# LED_for_Junction_Box.net
KiCad netlist of a schematic drawn in EAGLE
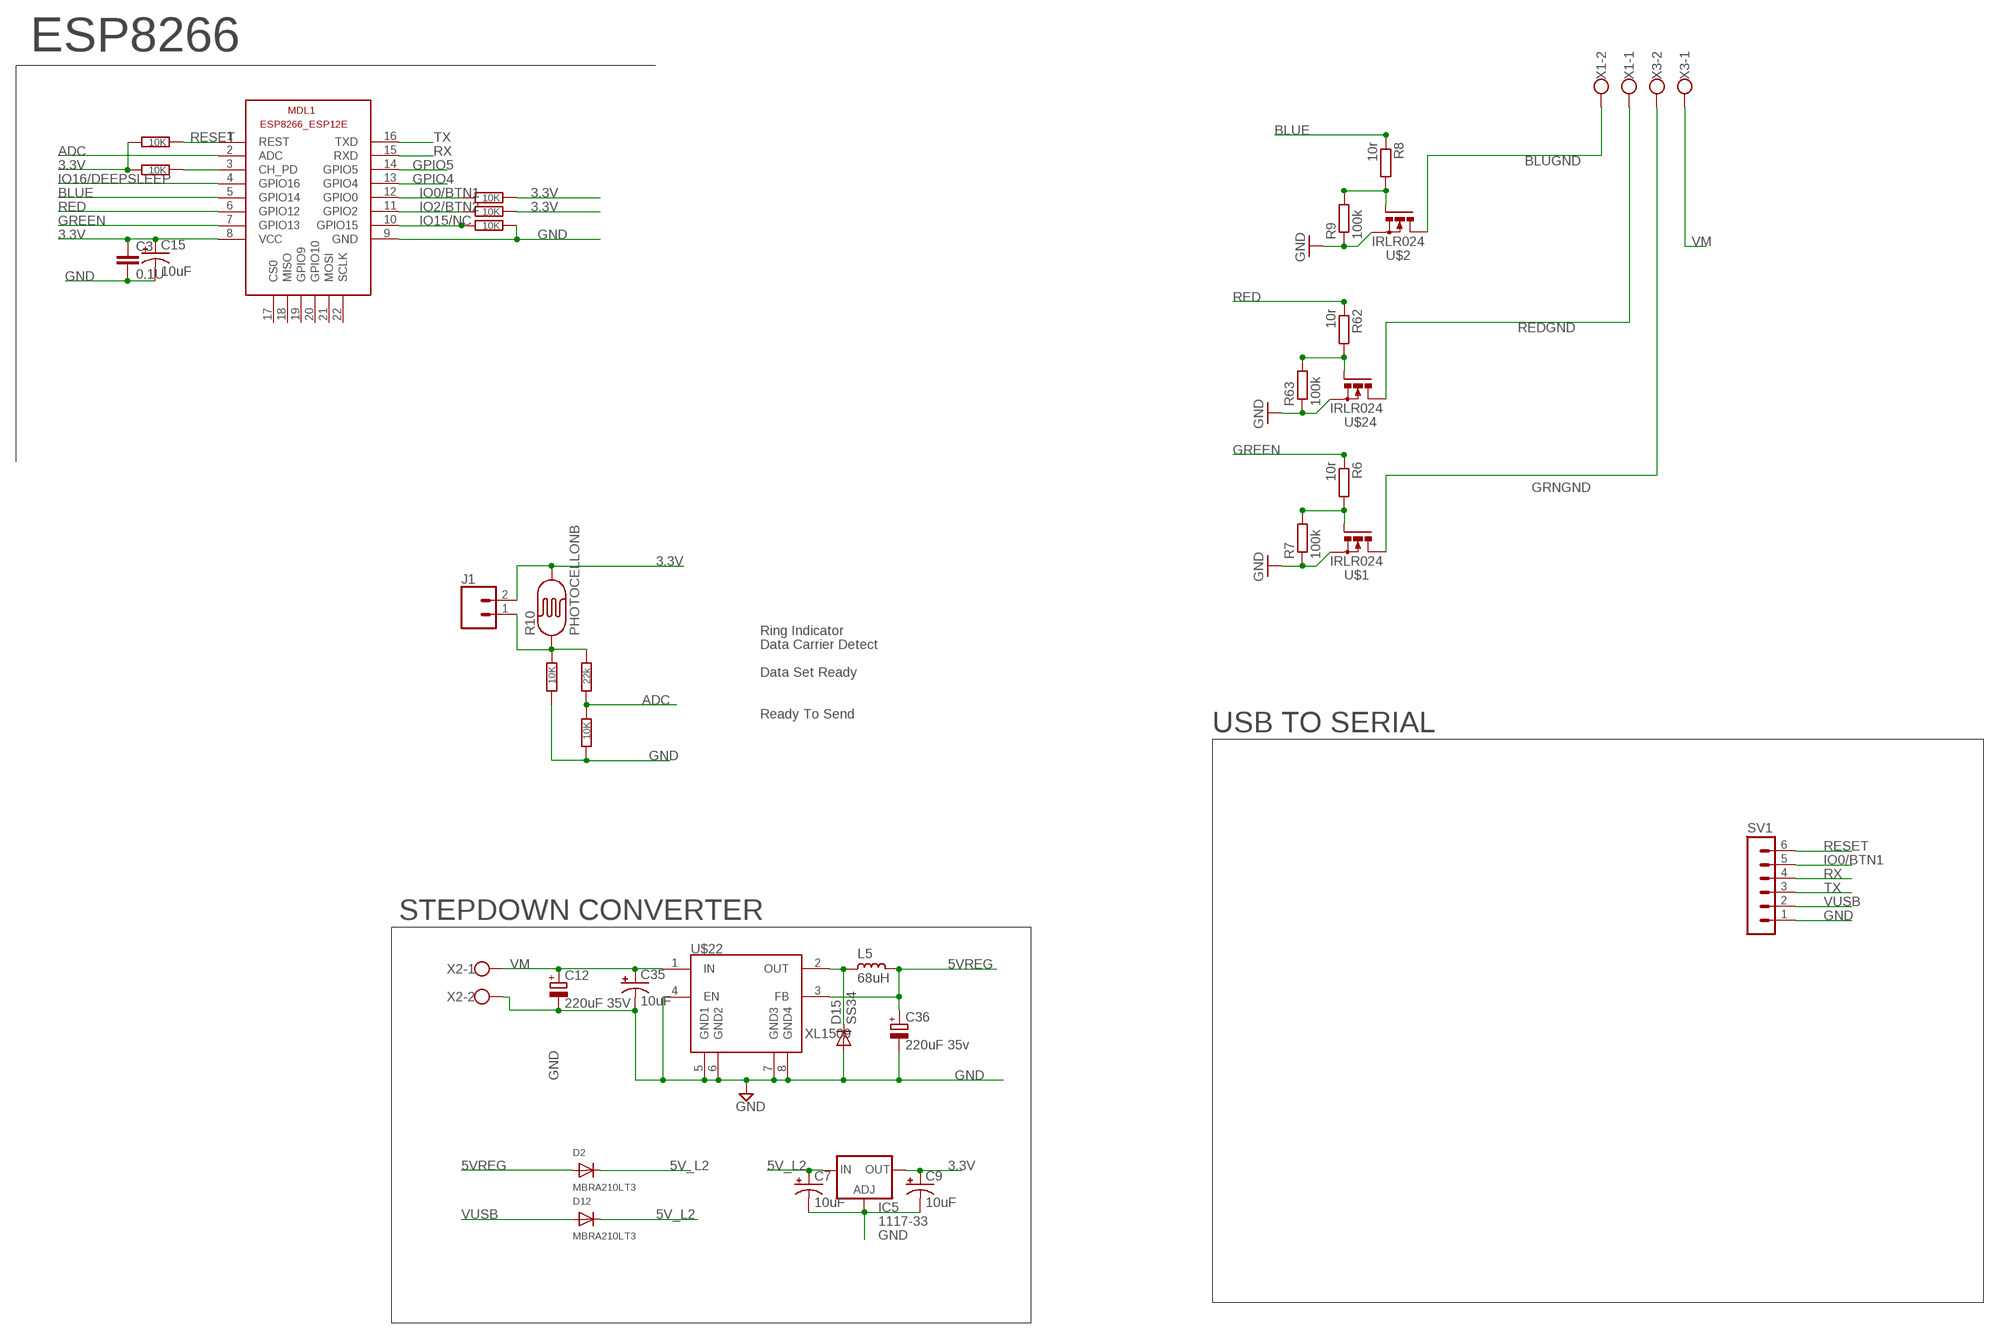
[diagram p0: schematic, sheet 1]

(export (version "E")
  (design (tool "Eeschema 10.0.6"))
  (components
    (comp (ref "C3")
      (value "0.1U")
      (footprint "eagle-import:C1206")
      (libsource (lib "eagle-import") (part "C-EUC1206"))
    )
    (comp (ref "C7")
      (value "10uF")
      (footprint "eagle-import:EIA3216")
      (libsource (lib "eagle-import") (part "CAP_POL1206"))
    )
    (comp (ref "C9")
      (value "10uF")
      (footprint "eagle-import:EIA3216")
      (libsource (lib "eagle-import") (part "CAP_POL1206"))
    )
    (comp (ref "C12")
      (value "220uF 35V")
      (footprint "eagle-import:E3,5-8")
      (libsource (lib "eagle-import") (part "CPOL-EUE3.5-8"))
    )
    (comp (ref "C15")
      (value "10uF")
      (footprint "eagle-import:EIA3216")
      (libsource (lib "eagle-import") (part "CAP_POL1206"))
    )
    (comp (ref "C35")
      (value "10uF")
      (footprint "eagle-import:EIA3216")
      (libsource (lib "eagle-import") (part "CAP_POL1206"))
    )
    (comp (ref "C36")
      (value "220uF 35v")
      (footprint "eagle-import:E3,5-8")
      (libsource (lib "eagle-import") (part "CPOL-EUE3.5-8"))
    )
    (comp (ref "D2")
      (value "MBRA210LT3")
      (footprint "eagle-import:SMADIODE")
      (libsource (lib "eagle-import") (part "DIODESMA"))
    )
    (comp (ref "D12")
      (value "MBRA210LT3")
      (footprint "eagle-import:SMADIODE")
      (libsource (lib "eagle-import") (part "DIODESMA"))
    )
    (comp (ref "D15")
      (value "SS34")
      (footprint "eagle-import:DO-214AC")
      (libsource (lib "eagle-import") (part "DIODE-DO-214AC"))
    )
    (comp (ref "IC5")
      (value "1117-33")
      (footprint "eagle-import:SOT223")
      (libsource (lib "eagle-import") (part "LD117A?S33TR"))
    )
    (comp (ref "J1")
      (value "CONN_02LOCK")
      (footprint "eagle-import:1X02_LOCK")
      (libsource (lib "eagle-import") (part "CONN_02LOCK"))
    )
    (comp (ref "L5")
      (value "68uH")
      (footprint "eagle-import:CD75")
      (libsource (lib "eagle-import") (part "L_CD75"))
    )
    (comp (ref "MDL1")
      (value "ESP8266-12EESP8266-ESP12E")
      (footprint "eagle-import:ESP8266-ESP12E")
      (libsource (lib "eagle-import") (part "ESP8266-12EESP8266-ESP12E"))
    )
    (comp (ref "R3")
      (value "22k")
      (footprint "eagle-import:R1206")
      (libsource (lib "eagle-import") (part "R-EU_R1206"))
    )
    (comp (ref "R4")
      (value "10K")
      (footprint "eagle-import:R1206")
      (libsource (lib "eagle-import") (part "R-EU_R1206"))
    )
    (comp (ref "R5")
      (value "10K")
      (footprint "eagle-import:R1206")
      (libsource (lib "eagle-import") (part "R-EU_R1206"))
    )
    (comp (ref "R6")
      (value "10r")
      (footprint "eagle-import:R1206")
      (libsource (lib "eagle-import") (part "resistor_R-EU_R1206"))
    )
    (comp (ref "R7")
      (value "100k")
      (footprint "eagle-import:R1206")
      (libsource (lib "eagle-import") (part "resistor_R-EU_R1206"))
    )
    (comp (ref "R8")
      (value "10r")
      (footprint "eagle-import:R1206")
      (libsource (lib "eagle-import") (part "resistor_R-EU_R1206"))
    )
    (comp (ref "R9")
      (value "100k")
      (footprint "eagle-import:R1206")
      (libsource (lib "eagle-import") (part "resistor_R-EU_R1206"))
    )
    (comp (ref "R10")
      (value "PHOTOCELLONB")
      (footprint "eagle-import:ON_BOARD")
      (libsource (lib "eagle-import") (part "PHOTOCELLONB"))
    )
    (comp (ref "R11")
      (value "10K")
      (footprint "eagle-import:R1206")
      (libsource (lib "eagle-import") (part "R-EU_R1206"))
    )
    (comp (ref "R12")
      (value "10K")
      (footprint "eagle-import:R1206")
      (libsource (lib "eagle-import") (part "R-EU_R1206"))
    )
    (comp (ref "R28")
      (value "10K")
      (footprint "eagle-import:R1206")
      (libsource (lib "eagle-import") (part "R-EU_R1206"))
    )
    (comp (ref "R29")
      (value "10K")
      (footprint "eagle-import:R1206")
      (libsource (lib "eagle-import") (part "R-EU_R1206"))
    )
    (comp (ref "R31")
      (value "10K")
      (footprint "eagle-import:R1206")
      (libsource (lib "eagle-import") (part "R-EU_R1206"))
    )
    (comp (ref "R62")
      (value "10r")
      (footprint "eagle-import:R1206")
      (libsource (lib "eagle-import") (part "resistor_R-EU_R1206"))
    )
    (comp (ref "R63")
      (value "100k")
      (footprint "eagle-import:R1206")
      (libsource (lib "eagle-import") (part "resistor_R-EU_R1206"))
    )
    (comp (ref "SV1")
      (value "MA06-1")
      (footprint "eagle-import:MA06-1")
      (libsource (lib "eagle-import") (part "MA06-1"))
    )
    (comp (ref "U$1")
      (value "IRLR024")
      (footprint "eagle-import:D-PAK_TO252AA")
      (libsource (lib "eagle-import") (part "N-POWER-MOSFETDPAK-MOSFET"))
    )
    (comp (ref "U$2")
      (value "IRLR024")
      (footprint "eagle-import:D-PAK_TO252AA")
      (libsource (lib "eagle-import") (part "N-POWER-MOSFETDPAK-MOSFET"))
    )
    (comp (ref "U$22")
      (value "XL1509")
      (footprint "eagle-import:SO08")
      (libsource (lib "eagle-import") (part "XL1509"))
    )
    (comp (ref "U$24")
      (value "IRLR024")
      (footprint "eagle-import:D-PAK_TO252AA")
      (libsource (lib "eagle-import") (part "N-POWER-MOSFETDPAK-MOSFET"))
    )
    (comp (ref "X1")
      (value "W237-102")
      (footprint "eagle-import:W237-102")
      (fields (field (name "MPN") "237-102"))
      (libsource (lib "eagle-import") (part "W237-102"))
    )
    (comp (ref "X2")
      (value "W237-102")
      (footprint "eagle-import:W237-102")
      (fields (field (name "MPN") "237-102"))
      (libsource (lib "eagle-import") (part "W237-102"))
    )
    (comp (ref "X3")
      (value "W237-102")
      (footprint "eagle-import:W237-102")
      (fields (field (name "MPN") "237-102"))
      (libsource (lib "eagle-import") (part "W237-102"))
    )
  )
  (nets
    (net (code "1") (name "/3.3V") (class "Default")
      (node (ref "C15") (pin "A") (pinfunction "+_A") (pintype "passive"))
      (node (ref "C3") (pin "1") (pinfunction "1_1") (pintype "passive"))
      (node (ref "C9") (pin "A") (pinfunction "+_A") (pintype "passive"))
      (node (ref "IC5") (pin "4") (pinfunction "OUT_4") (pintype "passive"))
      (node (ref "J1") (pin "2") (pinfunction "2_2") (pintype "passive"))
      (node (ref "MDL1") (pin "8") (pinfunction "VCC_8") (pintype "bidirectional"))
      (node (ref "R10") (pin "2") (pinfunction "P$2_2") (pintype "bidirectional"))
      (node (ref "R11") (pin "2") (pinfunction "2_2") (pintype "passive"))
      (node (ref "R12") (pin "2") (pinfunction "2_2") (pintype "passive"))
      (node (ref "R28") (pin "1") (pinfunction "1_1") (pintype "passive"))
      (node (ref "R29") (pin "1") (pinfunction "1_1") (pintype "passive"))
    )
    (net (code "2") (name "/5VREG") (class "Default")
      (node (ref "C36") (pin "+") (pinfunction "+_+") (pintype "passive"))
      (node (ref "D2") (pin "A") (pinfunction "A_A") (pintype "passive"))
      (node (ref "L5") (pin "1") (pinfunction "1_1") (pintype "passive"))
      (node (ref "U$22") (pin "3") (pinfunction "FB_3") (pintype "bidirectional"))
    )
    (net (code "3") (name "/5V_L2") (class "Default")
      (node (ref "C7") (pin "A") (pinfunction "+_A") (pintype "passive"))
      (node (ref "D12") (pin "C") (pinfunction "C_C") (pintype "passive"))
      (node (ref "D2") (pin "C") (pinfunction "C_C") (pintype "passive"))
      (node (ref "IC5") (pin "3") (pinfunction "IN_3") (pintype "input"))
    )
    (net (code "4") (name "/ADC") (class "Default")
      (node (ref "MDL1") (pin "2") (pinfunction "ADC_2") (pintype "bidirectional"))
      (node (ref "R3") (pin "1") (pinfunction "1_1") (pintype "passive"))
      (node (ref "R4") (pin "2") (pinfunction "2_2") (pintype "passive"))
    )
    (net (code "5") (name "/BLUE") (class "Default")
      (node (ref "MDL1") (pin "5") (pinfunction "GPIO14_5") (pintype "bidirectional"))
      (node (ref "R8") (pin "1") (pinfunction "1_1") (pintype "passive"))
    )
    (net (code "6") (name "/BLUGND") (class "Default")
      (node (ref "U$2") (pin "4") (pinfunction "D_4") (pintype "passive"))
      (node (ref "X1") (pin "2") (pinfunction "KL_2") (pintype "passive"))
    )
    (net (code "7") (name "/GPIO4") (class "Default")
      (node (ref "MDL1") (pin "13") (pinfunction "GPIO4_13") (pintype "bidirectional"))
    )
    (net (code "8") (name "/GPIO5") (class "Default")
      (node (ref "MDL1") (pin "14") (pinfunction "GPIO5_14") (pintype "bidirectional"))
    )
    (net (code "9") (name "/GREEN") (class "Default")
      (node (ref "MDL1") (pin "7") (pinfunction "GPIO13_7") (pintype "bidirectional"))
      (node (ref "R6") (pin "1") (pinfunction "1_1") (pintype "passive"))
    )
    (net (code "10") (name "/GRNGND") (class "Default")
      (node (ref "U$1") (pin "4") (pinfunction "D_4") (pintype "passive"))
      (node (ref "X3") (pin "2") (pinfunction "KL_2") (pintype "passive"))
    )
    (net (code "11") (name "/IO0{slash}BTN1") (class "Default")
      (node (ref "MDL1") (pin "12") (pinfunction "GPIO0_12") (pintype "bidirectional"))
      (node (ref "R12") (pin "1") (pinfunction "1_1") (pintype "passive"))
      (node (ref "SV1") (pin "5") (pinfunction "5_5") (pintype "passive"))
    )
    (net (code "12") (name "/IO2{slash}BTN2") (class "Default")
      (node (ref "MDL1") (pin "11") (pinfunction "GPIO2_11") (pintype "bidirectional"))
      (node (ref "R11") (pin "1") (pinfunction "1_1") (pintype "passive"))
    )
    (net (code "13") (name "/IO15{slash}NC") (class "Default")
      (node (ref "MDL1") (pin "10") (pinfunction "GPIO15_10") (pintype "bidirectional"))
      (node (ref "R31") (pin "1") (pinfunction "1_1") (pintype "passive"))
    )
    (net (code "14") (name "/IO16{slash}DEEPSLEEP") (class "Default")
      (node (ref "MDL1") (pin "4") (pinfunction "GPIO16_4") (pintype "bidirectional"))
    )
    (net (code "15") (name "/RED") (class "Default")
      (node (ref "MDL1") (pin "6") (pinfunction "GPIO12_6") (pintype "bidirectional"))
      (node (ref "R62") (pin "1") (pinfunction "1_1") (pintype "passive"))
    )
    (net (code "16") (name "/REDGND") (class "Default")
      (node (ref "U$24") (pin "4") (pinfunction "D_4") (pintype "passive"))
      (node (ref "X1") (pin "1") (pinfunction "KL_1") (pintype "passive"))
    )
    (net (code "17") (name "/RESET") (class "Default")
      (node (ref "MDL1") (pin "1") (pinfunction "REST_1") (pintype "bidirectional"))
      (node (ref "R29") (pin "2") (pinfunction "2_2") (pintype "passive"))
      (node (ref "SV1") (pin "6") (pinfunction "6_6") (pintype "passive"))
    )
    (net (code "18") (name "/RX") (class "Default")
      (node (ref "MDL1") (pin "15") (pinfunction "RXD_15") (pintype "bidirectional"))
      (node (ref "SV1") (pin "4") (pinfunction "4_4") (pintype "passive"))
    )
    (net (code "19") (name "/TX") (class "Default")
      (node (ref "MDL1") (pin "16") (pinfunction "TXD_16") (pintype "bidirectional"))
      (node (ref "SV1") (pin "3") (pinfunction "3_3") (pintype "passive"))
    )
    (net (code "20") (name "/VM") (class "Default")
      (node (ref "C12") (pin "+") (pinfunction "+_+") (pintype "passive"))
      (node (ref "C35") (pin "A") (pinfunction "+_A") (pintype "passive"))
      (node (ref "U$22") (pin "1") (pinfunction "IN_1") (pintype "bidirectional"))
      (node (ref "X2") (pin "1") (pinfunction "KL_1") (pintype "passive"))
      (node (ref "X3") (pin "1") (pinfunction "KL_1") (pintype "passive"))
    )
    (net (code "21") (name "/VUSB") (class "Default")
      (node (ref "D12") (pin "A") (pinfunction "A_A") (pintype "passive"))
      (node (ref "SV1") (pin "2") (pinfunction "2_2") (pintype "passive"))
    )
    (net (code "22") (name "GND") (class "Default")
      (node (ref "C12") (pin "-") (pinfunction "-_-") (pintype "passive"))
      (node (ref "C15") (pin "C") (pinfunction "-_C") (pintype "passive"))
      (node (ref "C3") (pin "2") (pinfunction "2_2") (pintype "passive"))
      (node (ref "C35") (pin "C") (pinfunction "-_C") (pintype "passive"))
      (node (ref "C36") (pin "-") (pinfunction "-_-") (pintype "passive"))
      (node (ref "C7") (pin "C") (pinfunction "-_C") (pintype "passive"))
      (node (ref "C9") (pin "C") (pinfunction "-_C") (pintype "passive"))
      (node (ref "D15") (pin "2") (pinfunction "A_2") (pintype "passive"))
      (node (ref "IC5") (pin "1") (pinfunction "ADJ_1") (pintype "input"))
      (node (ref "MDL1") (pin "9") (pinfunction "GND_9") (pintype "bidirectional"))
      (node (ref "R31") (pin "2") (pinfunction "2_2") (pintype "passive"))
      (node (ref "R4") (pin "1") (pinfunction "1_1") (pintype "passive"))
      (node (ref "R5") (pin "1") (pinfunction "1_1") (pintype "passive"))
      (node (ref "R63") (pin "1") (pinfunction "1_1") (pintype "passive"))
      (node (ref "R7") (pin "1") (pinfunction "1_1") (pintype "passive"))
      (node (ref "R9") (pin "1") (pinfunction "1_1") (pintype "passive"))
      (node (ref "SV1") (pin "1") (pinfunction "1_1") (pintype "passive"))
      (node (ref "U$1") (pin "3") (pinfunction "S_3") (pintype "passive"))
      (node (ref "U$2") (pin "3") (pinfunction "S_3") (pintype "passive"))
      (node (ref "U$22") (pin "4") (pinfunction "EN_4") (pintype "bidirectional"))
      (node (ref "U$22") (pin "5") (pinfunction "GND1_5") (pintype "bidirectional"))
      (node (ref "U$22") (pin "6") (pinfunction "GND2_6") (pintype "bidirectional"))
      (node (ref "U$22") (pin "7") (pinfunction "GND3_7") (pintype "bidirectional"))
      (node (ref "U$22") (pin "8") (pinfunction "GND4_8") (pintype "bidirectional"))
      (node (ref "U$24") (pin "3") (pinfunction "S_3") (pintype "passive"))
      (node (ref "X2") (pin "2") (pinfunction "KL_2") (pintype "passive"))
    )
    (net (code "23") (name "Net-(D15-C)") (class "Default")
      (node (ref "D15") (pin "1") (pinfunction "C_1") (pintype "passive"))
      (node (ref "L5") (pin "2") (pinfunction "2_2") (pintype "passive"))
      (node (ref "U$22") (pin "2") (pinfunction "OUT_2") (pintype "bidirectional"))
    )
    (net (code "24") (name "Net-(MDL1-CH_PD)") (class "Default")
      (node (ref "MDL1") (pin "3") (pinfunction "CH_PD_3") (pintype "bidirectional"))
      (node (ref "R28") (pin "2") (pinfunction "2_2") (pintype "passive"))
    )
    (net (code "25") (name "Net-(R10-P$1)") (class "Default")
      (node (ref "J1") (pin "1") (pinfunction "1_1") (pintype "passive"))
      (node (ref "R10") (pin "1") (pinfunction "P$1_1") (pintype "bidirectional"))
      (node (ref "R3") (pin "2") (pinfunction "2_2") (pintype "passive"))
      (node (ref "R5") (pin "2") (pinfunction "2_2") (pintype "passive"))
    )
    (net (code "26") (name "Net-(U$1-G)") (class "Default")
      (node (ref "R6") (pin "2") (pinfunction "2_2") (pintype "passive"))
      (node (ref "R7") (pin "2") (pinfunction "2_2") (pintype "passive"))
      (node (ref "U$1") (pin "1") (pinfunction "G_1") (pintype "passive"))
    )
    (net (code "27") (name "Net-(U$2-G)") (class "Default")
      (node (ref "R8") (pin "2") (pinfunction "2_2") (pintype "passive"))
      (node (ref "R9") (pin "2") (pinfunction "2_2") (pintype "passive"))
      (node (ref "U$2") (pin "1") (pinfunction "G_1") (pintype "passive"))
    )
    (net (code "28") (name "Net-(U$24-G)") (class "Default")
      (node (ref "R62") (pin "2") (pinfunction "2_2") (pintype "passive"))
      (node (ref "R63") (pin "2") (pinfunction "2_2") (pintype "passive"))
      (node (ref "U$24") (pin "1") (pinfunction "G_1") (pintype "passive"))
    )
    (net (code "29") (name "unconnected-(MDL1-CS0-Pad17)") (class "Default")
      (node (ref "MDL1") (pin "17") (pinfunction "CS0_17") (pintype "bidirectional"))
    )
    (net (code "30") (name "unconnected-(MDL1-GPIO9-Pad19)") (class "Default")
      (node (ref "MDL1") (pin "19") (pinfunction "GPIO9_19") (pintype "bidirectional"))
    )
    (net (code "31") (name "unconnected-(MDL1-GPIO10-Pad20)") (class "Default")
      (node (ref "MDL1") (pin "20") (pinfunction "GPIO10_20") (pintype "bidirectional"))
    )
    (net (code "32") (name "unconnected-(MDL1-MISO-Pad18)") (class "Default")
      (node (ref "MDL1") (pin "18") (pinfunction "MISO_18") (pintype "bidirectional"))
    )
    (net (code "33") (name "unconnected-(MDL1-MOSI-Pad21)") (class "Default")
      (node (ref "MDL1") (pin "21") (pinfunction "MOSI_21") (pintype "bidirectional"))
    )
    (net (code "34") (name "unconnected-(MDL1-SCLK-Pad22)") (class "Default")
      (node (ref "MDL1") (pin "22") (pinfunction "SCLK_22") (pintype "bidirectional"))
    )
  )
)
